# Power_Domain.net
KiCad netlist of a schematic drawn in Altium Designer
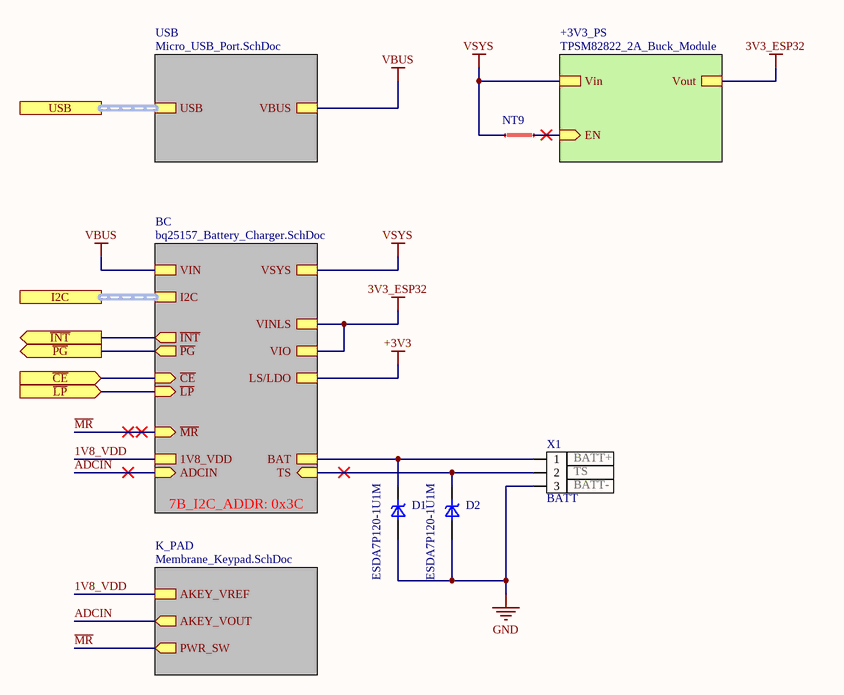
[diagram p0: Power_Domain.SchDoc]

(export (version "E")
  (design (tool "Eeschema 10.0.6"))
  (components
    (comp (ref "D1")
      (value "ESDA7P120-1U1M")
      (footprint "ST_QFN_1610")
      (description "11.5V Clamp 120A (8/20µs) Ipp Tvs Diode Surface Mount 1610")
      (fields (field (name "MANUFACTURER") "STMicroelectronics"))
      (libsource (lib "diodes_tvs") (part "TVS DIODE ESDA7P120-1U1M 5.5V 11.5V 1610"))
    )
    (comp (ref "D2")
      (value "ESDA7P120-1U1M")
      (footprint "ST_QFN_1610")
      (description "11.5V Clamp 120A (8/20µs) Ipp Tvs Diode Surface Mount 1610")
      (fields (field (name "MANUFACTURER") "STMicroelectronics"))
      (libsource (lib "diodes_tvs") (part "TVS DIODE ESDA7P120-1U1M 5.5V 11.5V 1610"))
    )
    (comp (ref "NT9")
      (value "Net Tie")
      (footprint "Net Tie 1x3mm")
      (libsource (lib "BLDC_Motor_Driver") (part "Net Tie Line"))
    )
    (comp (ref "X1")
      (value "BATT")
      (footprint "JST_S3B-ZR-SM4A-TF")
      (description "Connector Header Through Hole, Right Angle 3 position 0.059\" (1.50mm)")
      (fields
        (field (name "MANUFACTURER") "JST")
        (field (name "MANUFACTURER PART NUMBER") "S3B-ZR(LF)(SN)")
        (field (name "PIN_1") "BATT+")
        (field (name "PIN_2") "TS")
        (field (name "PIN_3") "BATT-")
      )
      (libsource (lib "Control_Board_Model_C201") (part "CONN HEADER TH R/A 3POS 1.5MM"))
    )
  )
  (nets
    (net (code "6") (name "/BAT") (class "Default")
      (node (ref "D1") (pin "1") (pinfunction "K_1") (pintype "passive"))
      (node (ref "X1") (pin "1") (pinfunction "1_1") (pintype "passive"))
    )
    (net (code "8") (name "/EN") (class "Default") (node (ref "NT9") (pin "1") (pintype "passive")))
    (net (code "14") (name "/TS") (class "Default")
      (node (ref "D2") (pin "1") (pinfunction "K_1") (pintype "passive"))
      (node (ref "X1") (pin "2") (pinfunction "2_2") (pintype "passive"))
    )
    (net (code "17") (name "GND") (class "Default")
      (node (ref "D1") (pin "2") (pinfunction "A_2") (pintype "passive"))
      (node (ref "D2") (pin "2") (pinfunction "A_2") (pintype "passive"))
      (node (ref "X1") (pin "3") (pinfunction "3_3") (pintype "passive"))
    )
    (net (code "19") (name "VSYS") (class "Default") (node (ref "NT9") (pin "2") (pintype "passive")))
  )
)
